# CATS-FAT-Overview.net
KiCad netlist of a schematic drawn in Altium Designer
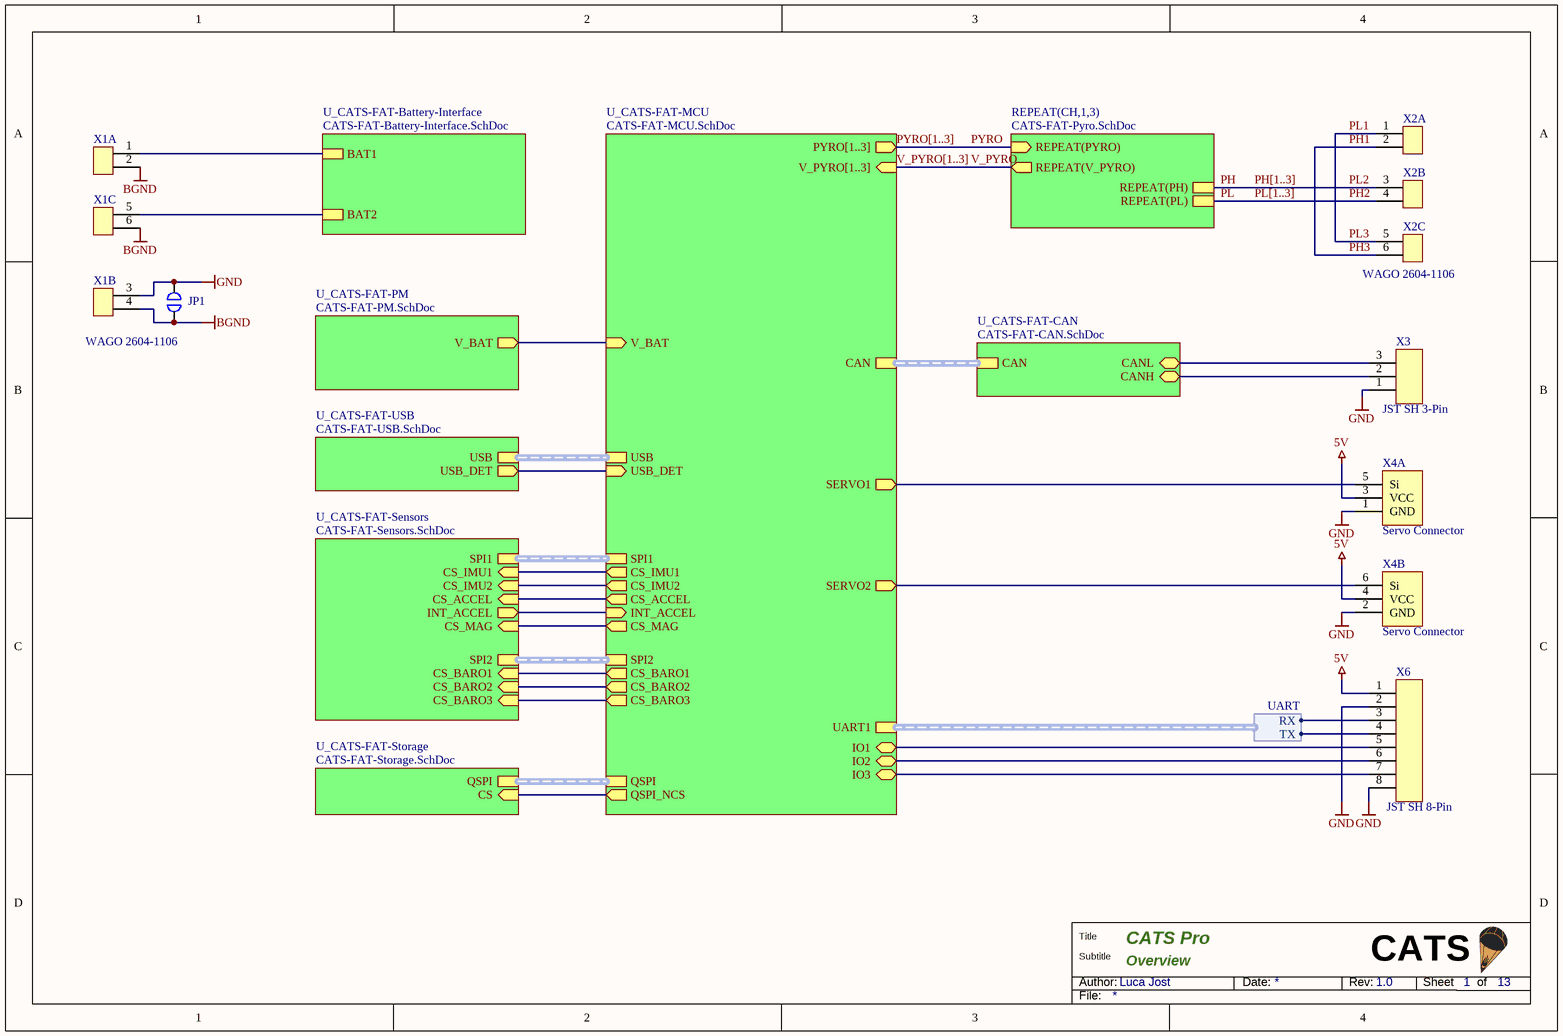
[diagram p0: CATS-FAT-Overview.SchDoc]

(export (version "E")
  (design (tool "Eeschema 10.0.6"))
  (components
    (comp (ref "JP1")
      (value "Jumper")
      (footprint "SMD Solder Jumper 1x2mm")
      (description "Single Position Jumper")
      (libsource (lib "Connectors") (part "Jumper-1"))
    )
    (comp (ref "X1")
      (value "WAGO 2604-1106")
      (footprint "THT PCB Terminal Wago 2604-1106")
      (description "PCB terminal blocks with levers and Push-in CAGE CLAMP® connection")
      (libsource (lib "") (part "WAGO 2604-1106_1"))
    )
    (comp (ref "X2")
      (value "WAGO 2604-1106")
      (footprint "THT PCB Terminal Wago 2604-1106")
      (description "PCB terminal blocks with levers and Push-in CAGE CLAMP® connection")
      (libsource (lib "Connectors") (part "WAGO 2604-1106"))
    )
    (comp (ref "X3")
      (value "JST SH 3-Pin")
      (footprint "SMD CONNECTOR JST-SR 3 PIN")
      (description "Crimp Style Connectors (Wire-to-Board type)")
      (libsource (lib "Connectors") (part "JST SH 3-Pin"))
    )
    (comp (ref "X4")
      (value "Servo Connector")
      (footprint "THT Stiftleiste 6-Pol (2x3) 90°")
      (description "6 Pin header for PWM servos")
      (libsource (lib "Connectors") (part "Servo Connector Dual"))
    )
    (comp (ref "X6")
      (value "JST SH 8-Pin")
      (footprint "SMD CONNECTOR JST-SR 8 PIN")
      (description "Crimp Style Connectors (Wire-to-Board type)")
      (libsource (lib "Connectors") (part "JST SH 8-Pin"))
    )
  )
  (nets
    (net (code "8") (name "/BAT1") (class "Default") (node (ref "X1") (pin "1") (pintype "passive")))
    (net (code "9") (name "/BAT2") (class "Default") (node (ref "X1") (pin "5") (pintype "passive")))
    (net (code "10") (name "/CANH") (class "Default")
      (node (ref "X3") (pin "2") (pinfunction "2_2") (pintype "passive"))
    )
    (net (code "11") (name "/CANL") (class "Default")
      (node (ref "X3") (pin "3") (pinfunction "3_3") (pintype "passive"))
    )
    (net (code "21") (name "/IO1") (class "Default")
      (node (ref "X6") (pin "5") (pinfunction "5_5") (pintype "passive"))
    )
    (net (code "22") (name "/IO2") (class "Default")
      (node (ref "X6") (pin "6") (pinfunction "6_6") (pintype "passive"))
    )
    (net (code "23") (name "/IO3") (class "Default")
      (node (ref "X6") (pin "7") (pinfunction "7_7") (pintype "passive"))
    )
    (net (code "25") (name "/PH1") (class "Default") (node (ref "X2") (pin "2") (pintype "passive")))
    (net (code "26") (name "/PH2") (class "Default") (node (ref "X2") (pin "4") (pintype "passive")))
    (net (code "27") (name "/PH3") (class "Default") (node (ref "X2") (pin "6") (pintype "passive")))
    (net (code "30") (name "/PL1") (class "Default") (node (ref "X2") (pin "1") (pintype "passive")))
    (net (code "31") (name "/PL2") (class "Default") (node (ref "X2") (pin "3") (pintype "passive")))
    (net (code "32") (name "/PL3") (class "Default") (node (ref "X2") (pin "5") (pintype "passive")))
    (net (code "38") (name "/RX") (class "Default")
      (node (ref "X6") (pin "3") (pinfunction "3_3") (pintype "passive"))
    )
    (net (code "39") (name "/SERVO1") (class "Default")
      (node (ref "X4") (pin "5") (pinfunction "Si_5") (pintype "passive"))
    )
    (net (code "40") (name "/SERVO2") (class "Default")
      (node (ref "X4") (pin "6") (pinfunction "Si_6") (pintype "passive"))
    )
    (net (code "43") (name "/TX") (class "Default")
      (node (ref "X6") (pin "4") (pinfunction "4_4") (pintype "passive"))
    )
    (net (code "50") (name "5V") (class "Default")
      (node (ref "X4") (pin "3") (pinfunction "VCC_3") (pintype "passive"))
      (node (ref "X4") (pin "4") (pinfunction "VCC_4") (pintype "passive"))
      (node (ref "X6") (pin "1") (pinfunction "1_1") (pintype "passive"))
    )
    (net (code "51") (name "BGND") (class "Default")
      (node (ref "JP1") (pin "2") (pintype "passive"))
      (node (ref "X1") (pin "2") (pintype "passive"))
      (node (ref "X1") (pin "4") (pintype "passive"))
      (node (ref "X1") (pin "6") (pintype "passive"))
    )
    (net (code "52") (name "GND") (class "Default")
      (node (ref "JP1") (pin "1") (pintype "passive"))
      (node (ref "X1") (pin "3") (pintype "passive"))
      (node (ref "X3") (pin "1") (pinfunction "1_1") (pintype "passive"))
      (node (ref "X4") (pin "1") (pinfunction "GND_1") (pintype "passive"))
      (node (ref "X4") (pin "2") (pinfunction "GND_2") (pintype "passive"))
      (node (ref "X6") (pin "2") (pinfunction "2_2") (pintype "passive"))
      (node (ref "X6") (pin "8") (pinfunction "8_8") (pintype "passive"))
    )
  )
)
